# 4_Programming_UART.net
KiCad netlist of a schematic drawn in Altium Designer
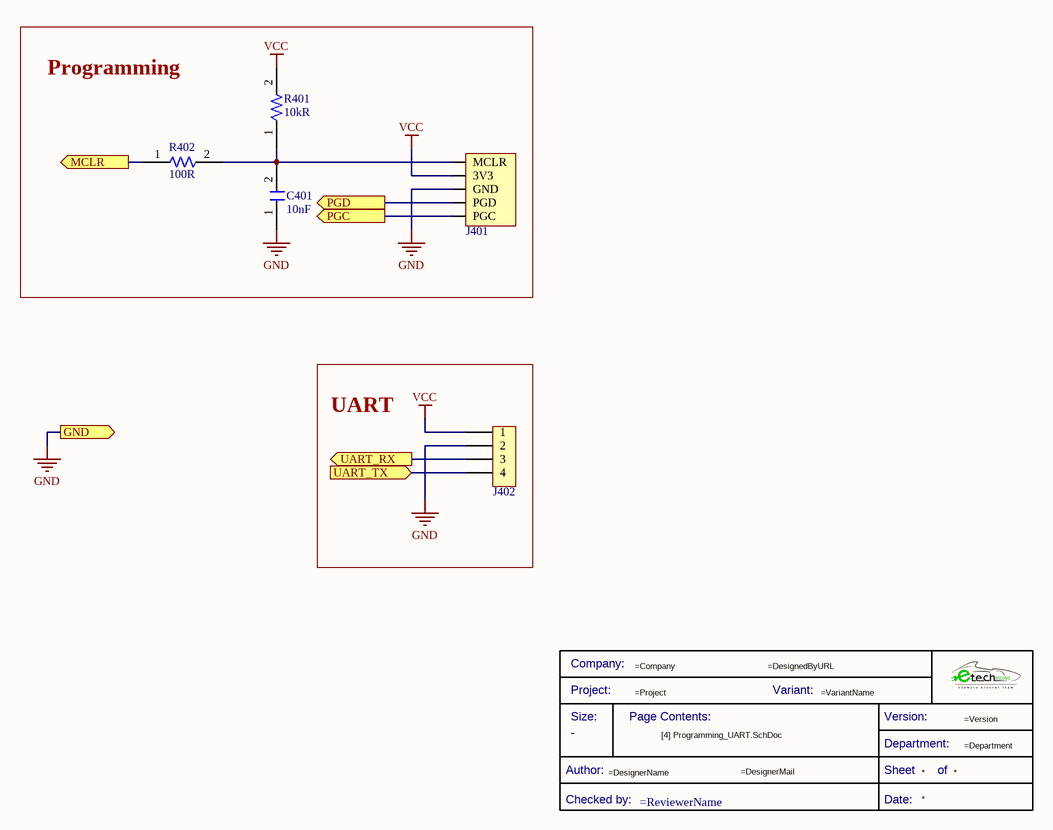
[diagram p0: [4] Programming_UART.SchDoc]

(export (version "E")
  (design (tool "Eeschema 10.0.6"))
  (components
    (comp (ref "*")
      (value "Title Block_template")
      (description "Standard Title Block")
      (fields (field (name "SIZE") "-"))
      (libsource (lib "e-Tech_Racing") (part "Title Block_template"))
    )
    (comp (ref "C401")
      (value "885012207092")
      (footprint "C0805FNPC-R")
      (description "Cap, 0.01ΜF, 50V, 10%, X7R, 0805")
      (fields
        (field (name "TOLERANCE") "10%")
        (field (name "CAPACITANCE") "10nF")
        (field (name ".CREATOR") "DR")
      )
      (libsource (lib "Passives") (part "C10n-50V-0805FNPC-X7R"))
    )
    (comp (ref "J401")
      (value "61300511121")
      (footprint "Bootloader_PIC_Connector")
      (description "THT Vertical Pin Header WR-PHD, Pitch 2.54 mm, Single Row, 5 pins")
      (fields (field (name "MANUFACTURER") "Molex"))
      (libsource (lib "Electromechanical") (part "J_Bootloader_PIC"))
    )
    (comp (ref "J402")
      (value "61300411121")
      (footprint "J_PinHeader_1x4")
      (description "CONN HEADER 4 POS 2.54")
      (fields (field (name ".CREATOR") "AC"))
      (libsource (lib "Electromechanical") (part "J_UART"))
    )
    (comp (ref "R401")
      (value "CR0805-JW-103ELF")
      (footprint "R0805FTK")
      (fields
        (field (name "TOLERANCE") "5%")
        (field (name "RESISTANCE") "10kR")
        (field (name ".CREATOR") "DR")
      )
      (libsource (lib "Passives") (part "R10k-0805FTK"))
    )
    (comp (ref "R402")
      (value "CR0805-FX-1000ELF")
      (footprint "R0805FTK")
      (description "Res Thick Film 0805 100 Ohm 1% 1/8W ±100ppm/°C Molded SMD SMD Paper Tape on Plastic Reel")
      (fields
        (field (name "TOLERANCE") "1%")
        (field (name "RESISTANCE") "100R")
        (field (name ".CREATOR") "DR")
      )
      (libsource (lib "Passives") (part "R100-0805FTK"))
    )
  )
  (nets
    (net (code "1") (name "/MCLR") (class "Default")
      (node (ref "R402") (pin "1") (pinfunction "1_1") (pintype "passive"))
    )
    (net (code "2") (name "/PGC") (class "Default")
      (node (ref "J401") (pin "PGC") (pinfunction "PGC_PGC") (pintype "passive"))
    )
    (net (code "3") (name "/PGD") (class "Default")
      (node (ref "J401") (pin "PGD") (pinfunction "PGD_PGD") (pintype "passive"))
    )
    (net (code "4") (name "/UART_RX") (class "Default")
      (node (ref "J402") (pin "3") (pinfunction "3_3") (pintype "passive"))
    )
    (net (code "5") (name "/UART_TX") (class "Default")
      (node (ref "J402") (pin "4") (pinfunction "4_4") (pintype "passive"))
    )
    (net (code "6") (name "GND") (class "Default")
      (node (ref "C401") (pin "1") (pinfunction "1_1") (pintype "passive"))
      (node (ref "J401") (pin "GND") (pinfunction "GND_GND") (pintype "passive"))
      (node (ref "J402") (pin "2") (pinfunction "2_2") (pintype "passive"))
    )
    (net (code "7") (name "Net-(C401-Pad2)") (class "Default")
      (node (ref "C401") (pin "2") (pinfunction "2_2") (pintype "passive"))
      (node (ref "J401") (pin "MCLR") (pinfunction "MCLR_MCLR") (pintype "passive"))
      (node (ref "R401") (pin "1") (pinfunction "1_1") (pintype "passive"))
      (node (ref "R402") (pin "2") (pinfunction "2_2") (pintype "passive"))
    )
    (net (code "8") (name "VCC") (class "Default")
      (node (ref "J401") (pin "3V3") (pinfunction "3V3_3V3") (pintype "passive"))
      (node (ref "J402") (pin "1") (pinfunction "1_1") (pintype "passive"))
      (node (ref "R401") (pin "2") (pinfunction "2_2") (pintype "passive"))
    )
  )
)
